# MAZ000163_-_Diagrama_el_ctrico.net
KiCad netlist of a schematic drawn in Altium Designer
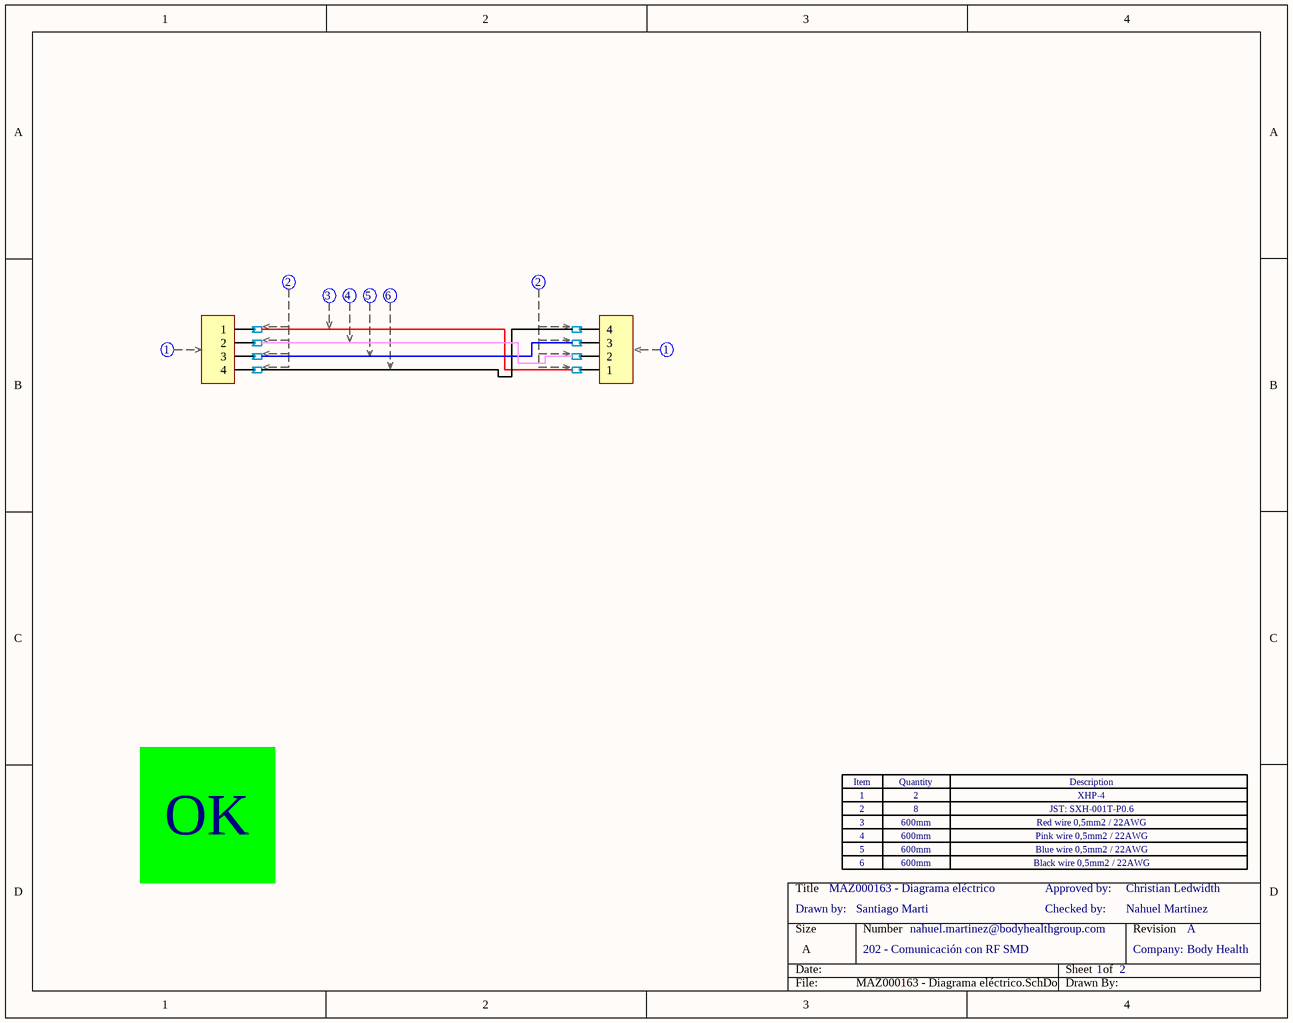
[diagram p0: MAZ000163 - Diagrama eléctrico.SchDoc]

(export (version "E")
  (design (tool "Eeschema 10.0.6"))
  (components
    (comp (ref "Cab1") (value "Cable") (libsource (lib "LibreriaParaPlanos") (part "Cable")))
    (comp (ref "Cab2") (value "Cable") (libsource (lib "LibreriaParaPlanos") (part "Cable")))
    (comp (ref "Cab3") (value "Cable") (libsource (lib "LibreriaParaPlanos") (part "Cable")))
    (comp (ref "Cab4") (value "Cable") (libsource (lib "LibreriaParaPlanos") (part "Cable")))
    (comp (ref "Con1")
      (value "XHP-4")
      (description "CONN HOUSING 2.5MM 4POS")
      (libsource (lib "") (part "XHP-4_1"))
    )
    (comp (ref "Con2")
      (value "CST-100-4")
      (description "CONN RCPT HSNG 4POS CST-100 II")
      (libsource (lib "LibreriaParaPlanos") (part "CST-100-4"))
    )
    (comp (ref "Con3")
      (value "XHP-4")
      (description "CONN HOUSING 2.5MM 4POS")
      (libsource (lib "LibreriaParaPlanos") (part "XHP-4"))
    )
    (comp (ref "Soc1")
      (value "sock_XHP_SXH-002T-P0.6")
      (description "CONN SOCKET 26-30AWG CRIMP TIN")
      (libsource (lib "LibreriaParaPlanos") (part "sock_XHP_SXH-002T-P0.6"))
    )
    (comp (ref "Soc2")
      (value "sock_CST_1375819-1")
      (description "CONN SOCKET 22-26AWG CRIMP TIN")
      (libsource (lib "LibreriaParaPlanos") (part "sock_CST_1375819-1"))
    )
    (comp (ref "Soc3")
      (value "sock_XHP_SXH-002T-P0.6")
      (description "CONN SOCKET 26-30AWG CRIMP TIN")
      (libsource (lib "LibreriaParaPlanos") (part "sock_XHP_SXH-002T-P0.6"))
    )
    (comp (ref "Soc4")
      (value "sock_XHP_SXH-002T-P0.6")
      (description "CONN SOCKET 26-30AWG CRIMP TIN")
      (libsource (lib "LibreriaParaPlanos") (part "sock_XHP_SXH-002T-P0.6"))
    )
    (comp (ref "Soc5")
      (value "sock_XHP_SXH-002T-P0.6")
      (description "CONN SOCKET 26-30AWG CRIMP TIN")
      (libsource (lib "LibreriaParaPlanos") (part "sock_XHP_SXH-002T-P0.6"))
    )
    (comp (ref "Soc6")
      (value "sock_XHP_SXH-002T-P0.6")
      (description "CONN SOCKET 26-30AWG CRIMP TIN")
      (libsource (lib "LibreriaParaPlanos") (part "sock_XHP_SXH-002T-P0.6"))
    )
    (comp (ref "Soc7")
      (value "sock_XHP_SXH-002T-P0.6")
      (description "CONN SOCKET 26-30AWG CRIMP TIN")
      (libsource (lib "LibreriaParaPlanos") (part "sock_XHP_SXH-002T-P0.6"))
    )
    (comp (ref "Soc8")
      (value "sock_XHP_SXH-002T-P0.6")
      (description "CONN SOCKET 26-30AWG CRIMP TIN")
      (libsource (lib "LibreriaParaPlanos") (part "sock_XHP_SXH-002T-P0.6"))
    )
    (comp (ref "Soc9")
      (value "sock_XHP_SXH-002T-P0.6")
      (description "CONN SOCKET 26-30AWG CRIMP TIN")
      (libsource (lib "LibreriaParaPlanos") (part "sock_XHP_SXH-002T-P0.6"))
    )
    (comp (ref "Zoc1")
      (value "Zócalo_Header")
      (description "Header para el zócalo de referencias")
      (libsource (lib "LibreriaParaPlanos") (part "Zócalo_Header"))
    )
    (comp (ref "Zoc2")
      (value "Zócalo_Item")
      (description "Ítem para el zócalo de referencias")
      (libsource (lib "LibreriaParaPlanos") (part "Zócalo_Item"))
    )
    (comp (ref "Zoc4")
      (value "Zócalo_Item")
      (description "Ítem para el zócalo de referencias")
      (libsource (lib "LibreriaParaPlanos") (part "Zócalo_Item"))
    )
    (comp (ref "Zoc6")
      (value "Zócalo_Item")
      (description "Ítem para el zócalo de referencias")
      (libsource (lib "LibreriaParaPlanos") (part "Zócalo_Item"))
    )
    (comp (ref "Zoc7")
      (value "Zócalo_Item")
      (description "Ítem para el zócalo de referencias")
      (libsource (lib "LibreriaParaPlanos") (part "Zócalo_Item"))
    )
    (comp (ref "Zoc8")
      (value "Zócalo_Item")
      (description "Ítem para el zócalo de referencias")
      (libsource (lib "LibreriaParaPlanos") (part "Zócalo_Item"))
    )
    (comp (ref "Zoc9")
      (value "Zócalo_Item")
      (description "Ítem para el zócalo de referencias")
      (libsource (lib "LibreriaParaPlanos") (part "Zócalo_Item"))
    )
  )
  (nets
    (net (code "1") (name "Net-(Con1-Pad1)") (class "Default")
      (node (ref "Con1") (pin "1") (pinfunction "1_1") (pintype "passive"))
      (node (ref "Soc1") (pin "0") (pinfunction "0_0") (pintype "passive"))
    )
    (net (code "2") (name "Net-(Con1-Pad2)") (class "Default")
      (node (ref "Con1") (pin "2") (pinfunction "2_2") (pintype "passive"))
      (node (ref "Soc3") (pin "0") (pinfunction "0_0") (pintype "passive"))
    )
    (net (code "3") (name "Net-(Con1-Pad3)") (class "Default")
      (node (ref "Con1") (pin "3") (pinfunction "3_3") (pintype "passive"))
      (node (ref "Soc5") (pin "0") (pinfunction "0_0") (pintype "passive"))
    )
    (net (code "4") (name "Net-(Con1-Pad4)") (class "Default")
      (node (ref "Con1") (pin "4") (pinfunction "4_4") (pintype "passive"))
      (node (ref "Soc7") (pin "0") (pinfunction "0_0") (pintype "passive"))
    )
    (net (code "5") (name "Net-(Con3-Pad1)") (class "Default")
      (node (ref "Con3") (pin "1") (pinfunction "1_1") (pintype "passive"))
      (node (ref "Soc9") (pin "0") (pinfunction "0_0") (pintype "passive"))
    )
    (net (code "6") (name "Net-(Con3-Pad2)") (class "Default")
      (node (ref "Con3") (pin "2") (pinfunction "2_2") (pintype "passive"))
      (node (ref "Soc8") (pin "0") (pinfunction "0_0") (pintype "passive"))
    )
    (net (code "7") (name "Net-(Con3-Pad3)") (class "Default")
      (node (ref "Con3") (pin "3") (pinfunction "3_3") (pintype "passive"))
      (node (ref "Soc6") (pin "0") (pinfunction "0_0") (pintype "passive"))
    )
    (net (code "8") (name "Net-(Con3-Pad4)") (class "Default")
      (node (ref "Con3") (pin "4") (pinfunction "4_4") (pintype "passive"))
      (node (ref "Soc4") (pin "0") (pinfunction "0_0") (pintype "passive"))
    )
    (net (code "9") (name "Net-(Soc1-Pad1)") (class "Default")
      (node (ref "Soc1") (pin "1") (pinfunction "1_1") (pintype "passive"))
      (node (ref "Soc9") (pin "1") (pinfunction "1_1") (pintype "passive"))
    )
    (net (code "10") (name "Net-(Soc3-Pad1)") (class "Default")
      (node (ref "Soc3") (pin "1") (pinfunction "1_1") (pintype "passive"))
      (node (ref "Soc8") (pin "1") (pinfunction "1_1") (pintype "passive"))
    )
    (net (code "11") (name "Net-(Soc4-Pad1)") (class "Default")
      (node (ref "Soc4") (pin "1") (pinfunction "1_1") (pintype "passive"))
      (node (ref "Soc7") (pin "1") (pinfunction "1_1") (pintype "passive"))
    )
    (net (code "12") (name "Net-(Soc5-Pad1)") (class "Default")
      (node (ref "Soc5") (pin "1") (pinfunction "1_1") (pintype "passive"))
      (node (ref "Soc6") (pin "1") (pinfunction "1_1") (pintype "passive"))
    )
  )
)
